# CapacitanceSelector.net
KiCad netlist of a schematic drawn in EAGLE
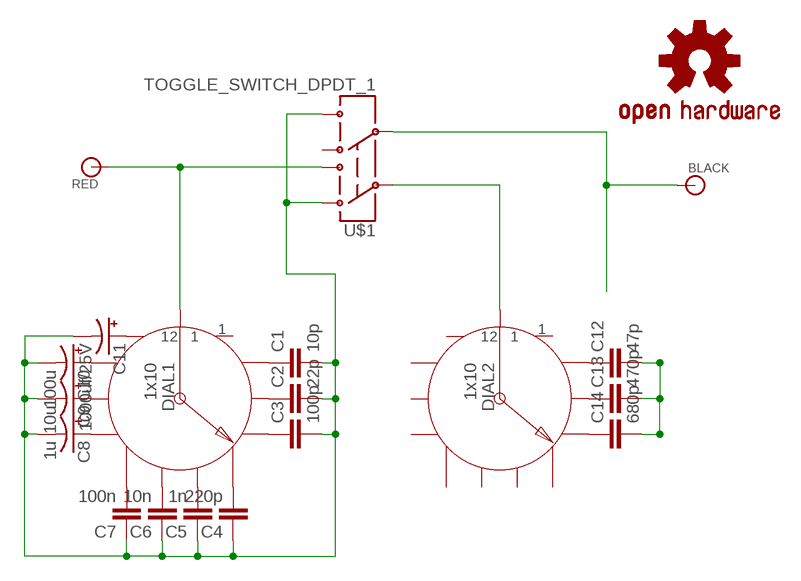
[diagram p0: schematic, sheet 1]

(export (version "E")
  (design (tool "Eeschema 10.0.6"))
  (components
    (comp (ref "BLACK")
      (value "BANANA_CONN")
      (footprint "eagle-import:BANANA_CONN")
      (libsource (lib "eagle-import") (part "BANANA_CONN"))
    )
    (comp (ref "C1")
      (value "10p")
      (footprint "eagle-import:CAP-PTH-SMALL-KIT")
      (libsource (lib "eagle-import") (part "0.1UF-50V-20%(PTH)KIT-EZ"))
    )
    (comp (ref "C2")
      (value "22p")
      (footprint "eagle-import:CAP-PTH-SMALL-KIT")
      (libsource (lib "eagle-import") (part "0.1UF-50V-20%(PTH)KIT-EZ"))
    )
    (comp (ref "C3")
      (value "100p")
      (footprint "eagle-import:CAP-PTH-SMALL-KIT")
      (libsource (lib "eagle-import") (part "0.1UF-50V-20%(PTH)KIT-EZ"))
    )
    (comp (ref "C4")
      (value "220p")
      (footprint "eagle-import:CAP-PTH-SMALL-KIT")
      (libsource (lib "eagle-import") (part "0.1UF-50V-20%(PTH)KIT-EZ"))
    )
    (comp (ref "C5")
      (value "1n")
      (footprint "eagle-import:CAP-PTH-SMALL-KIT")
      (libsource (lib "eagle-import") (part "0.1UF-50V-20%(PTH)KIT-EZ"))
    )
    (comp (ref "C6")
      (value "10n")
      (footprint "eagle-import:CAP-PTH-SMALL-KIT")
      (libsource (lib "eagle-import") (part "0.1UF-50V-20%(PTH)KIT-EZ"))
    )
    (comp (ref "C7")
      (value "100n")
      (footprint "eagle-import:CAP-PTH-SMALL-KIT")
      (libsource (lib "eagle-import") (part "0.1UF-50V-20%(PTH)KIT-EZ"))
    )
    (comp (ref "C8")
      (value "1u")
      (footprint "eagle-import:CPOL-RADIAL-10UF-25V-KIT")
      (libsource (lib "eagle-import") (part "10UF-25V-20%(PTH)KIT"))
    )
    (comp (ref "C9")
      (value "10u")
      (footprint "eagle-import:CPOL-RADIAL-10UF-25V-KIT")
      (libsource (lib "eagle-import") (part "10UF-25V-20%(PTH)KIT"))
    )
    (comp (ref "C10")
      (value "100u")
      (footprint "eagle-import:CPOL-RADIAL-10UF-25V-KIT")
      (libsource (lib "eagle-import") (part "10UF-25V-20%(PTH)KIT"))
    )
    (comp (ref "C11")
      (value "1000uf/25V")
      (footprint "eagle-import:CPOL-RADIAL-1000UF-25V-KIT")
      (libsource (lib "eagle-import") (part "1000UF-25V(PTH)KIT"))
    )
    (comp (ref "C12")
      (value "47p")
      (footprint "eagle-import:AXIAL-5MM")
      (libsource (lib "eagle-import") (part "CAP_"))
    )
    (comp (ref "C13")
      (value "470p")
      (footprint "eagle-import:CAP-PTH-SMALL-KIT")
      (libsource (lib "eagle-import") (part "0.1UF-50V-20%(PTH)KIT-EZ"))
    )
    (comp (ref "C14")
      (value "680p")
      (footprint "eagle-import:CAP-PTH-SMALL-KIT")
      (libsource (lib "eagle-import") (part "0.1UF-50V-20%(PTH)KIT-EZ"))
    )
    (comp (ref "DIAL1")
      (value "1x10")
      (footprint "eagle-import:ROTARY_SWITCH_1X12")
      (libsource (lib "eagle-import") (part "SWITCH_ROTARY_1X12"))
    )
    (comp (ref "DIAL2")
      (value "1x10")
      (footprint "eagle-import:ROTARY_SWITCH_1X12")
      (libsource (lib "eagle-import") (part "SWITCH_ROTARY_1X12"))
    )
    (comp (ref "LOGO1")
      (value "OSHW-LOGOL")
      (footprint "eagle-import:OSHW-LOGO-L")
      (libsource (lib "eagle-import") (part "OSHW-LOGOL"))
    )
    (comp (ref "RED")
      (value "BANANA_CONN")
      (footprint "eagle-import:BANANA_CONN")
      (libsource (lib "eagle-import") (part "BANANA_CONN"))
    )
    (comp (ref "U$1")
      (value "TOGGLE_SWITCH_DPDT_1")
      (footprint "eagle-import:TOGGLE_SWITCH_1")
      (libsource (lib "eagle-import") (part "TOGGLE_SWITCH_DPDT_1"))
    )
  )
  (nets
    (net (code "1") (name "Net-(BLACK-1)") (class "Default")
      (node (ref "BLACK") (pin "P$1") (pinfunction "1_P$1") (pintype "passive"))
      (node (ref "U$1") (pin "P$4") (pinfunction "5_P$4") (pintype "bidirectional"))
    )
    (net (code "2") (name "Net-(C1-Pad1)") (class "Default")
      (node (ref "C1") (pin "1") (pinfunction "1_1") (pintype "passive"))
      (node (ref "DIAL1") (pin "2") (pinfunction "2_2") (pintype "bidirectional"))
    )
    (net (code "3") (name "Net-(C2-Pad1)") (class "Default")
      (node (ref "C2") (pin "1") (pinfunction "1_1") (pintype "passive"))
      (node (ref "DIAL1") (pin "3") (pinfunction "3_3") (pintype "bidirectional"))
    )
    (net (code "4") (name "Net-(C3-Pad1)") (class "Default")
      (node (ref "C3") (pin "1") (pinfunction "1_1") (pintype "passive"))
      (node (ref "DIAL1") (pin "4") (pinfunction "4_4") (pintype "bidirectional"))
    )
    (net (code "5") (name "Net-(C4-Pad2)") (class "Default")
      (node (ref "C4") (pin "2") (pinfunction "2_2") (pintype "passive"))
      (node (ref "DIAL1") (pin "5") (pinfunction "5_5") (pintype "bidirectional"))
    )
    (net (code "6") (name "Net-(C5-Pad2)") (class "Default")
      (node (ref "C5") (pin "2") (pinfunction "2_2") (pintype "passive"))
      (node (ref "DIAL1") (pin "6") (pinfunction "6_6") (pintype "bidirectional"))
    )
    (net (code "7") (name "Net-(C6-Pad2)") (class "Default")
      (node (ref "C6") (pin "2") (pinfunction "2_2") (pintype "passive"))
      (node (ref "DIAL1") (pin "7") (pinfunction "7_7") (pintype "bidirectional"))
    )
    (net (code "8") (name "Net-(C7-Pad2)") (class "Default")
      (node (ref "C7") (pin "2") (pinfunction "2_2") (pintype "passive"))
      (node (ref "DIAL1") (pin "8") (pinfunction "8_8") (pintype "bidirectional"))
    )
    (net (code "9") (name "Net-(C8-+)") (class "Default")
      (node (ref "C8") (pin "1") (pinfunction "+_1") (pintype "passive"))
      (node (ref "DIAL1") (pin "9") (pinfunction "9_9") (pintype "bidirectional"))
    )
    (net (code "10") (name "Net-(C9-+)") (class "Default")
      (node (ref "C9") (pin "1") (pinfunction "+_1") (pintype "passive"))
      (node (ref "DIAL1") (pin "10") (pinfunction "10_10") (pintype "bidirectional"))
    )
    (net (code "11") (name "Net-(C10-+)") (class "Default")
      (node (ref "C10") (pin "1") (pinfunction "+_1") (pintype "passive"))
      (node (ref "DIAL1") (pin "11") (pinfunction "11_11") (pintype "bidirectional"))
    )
    (net (code "12") (name "Net-(C10--)") (class "Default")
      (node (ref "C1") (pin "2") (pinfunction "2_2") (pintype "passive"))
      (node (ref "C10") (pin "2") (pinfunction "-_2") (pintype "passive"))
      (node (ref "C11") (pin "-") (pinfunction "-_-") (pintype "passive"))
      (node (ref "C2") (pin "2") (pinfunction "2_2") (pintype "passive"))
      (node (ref "C3") (pin "2") (pinfunction "2_2") (pintype "passive"))
      (node (ref "C4") (pin "1") (pinfunction "1_1") (pintype "passive"))
      (node (ref "C5") (pin "1") (pinfunction "1_1") (pintype "passive"))
      (node (ref "C6") (pin "1") (pinfunction "1_1") (pintype "passive"))
      (node (ref "C7") (pin "1") (pinfunction "1_1") (pintype "passive"))
      (node (ref "C8") (pin "2") (pinfunction "-_2") (pintype "passive"))
      (node (ref "C9") (pin "2") (pinfunction "-_2") (pintype "passive"))
      (node (ref "U$1") (pin "P$1") (pinfunction "1_P$1") (pintype "bidirectional"))
      (node (ref "U$1") (pin "P$6") (pinfunction "6_P$6") (pintype "bidirectional"))
    )
    (net (code "13") (name "Net-(C11-Pad+)") (class "Default")
      (node (ref "C11") (pin "+") (pinfunction "+_+") (pintype "passive"))
      (node (ref "DIAL1") (pin "12") (pinfunction "12_12") (pintype "bidirectional"))
    )
    (net (code "14") (name "Net-(C12-1)") (class "Default")
      (node (ref "C12") (pin "P$1") (pinfunction "1_P$1") (pintype "passive"))
      (node (ref "DIAL2") (pin "2") (pinfunction "2_2") (pintype "bidirectional"))
    )
    (net (code "15") (name "Net-(C12-2)") (class "Default")
      (node (ref "C12") (pin "P$2") (pinfunction "2_P$2") (pintype "passive"))
      (node (ref "C13") (pin "2") (pinfunction "2_2") (pintype "passive"))
      (node (ref "C14") (pin "2") (pinfunction "2_2") (pintype "passive"))
    )
    (net (code "16") (name "Net-(C13-Pad1)") (class "Default")
      (node (ref "C13") (pin "1") (pinfunction "1_1") (pintype "passive"))
      (node (ref "DIAL2") (pin "3") (pinfunction "3_3") (pintype "bidirectional"))
    )
    (net (code "17") (name "Net-(C14-Pad1)") (class "Default")
      (node (ref "C14") (pin "1") (pinfunction "1_1") (pintype "passive"))
      (node (ref "DIAL2") (pin "4") (pinfunction "4_4") (pintype "bidirectional"))
    )
    (net (code "18") (name "Net-(RED-1)") (class "Default")
      (node (ref "DIAL1") (pin "COMMON") (pinfunction "COMMON_COMMON") (pintype "bidirectional"))
      (node (ref "RED") (pin "P$1") (pinfunction "1_P$1") (pintype "passive"))
      (node (ref "U$1") (pin "P$2") (pinfunction "3_P$2") (pintype "bidirectional"))
    )
    (net (code "19") (name "Net-(U$1-2)") (class "Default")
      (node (ref "DIAL2") (pin "COMMON") (pinfunction "COMMON_COMMON") (pintype "bidirectional"))
      (node (ref "U$1") (pin "P$3") (pinfunction "2_P$3") (pintype "bidirectional"))
    )
    (net (code "20") (name "unconnected-(DIAL1-Pad1)") (class "Default")
      (node (ref "DIAL1") (pin "1") (pinfunction "1_1") (pintype "bidirectional"))
    )
    (net (code "21") (name "unconnected-(DIAL2-Pad1)") (class "Default")
      (node (ref "DIAL2") (pin "1") (pinfunction "1_1") (pintype "bidirectional"))
    )
    (net (code "22") (name "unconnected-(DIAL2-Pad5)") (class "Default")
      (node (ref "DIAL2") (pin "5") (pinfunction "5_5") (pintype "bidirectional"))
    )
    (net (code "23") (name "unconnected-(DIAL2-Pad6)") (class "Default")
      (node (ref "DIAL2") (pin "6") (pinfunction "6_6") (pintype "bidirectional"))
    )
    (net (code "24") (name "unconnected-(DIAL2-Pad7)") (class "Default")
      (node (ref "DIAL2") (pin "7") (pinfunction "7_7") (pintype "bidirectional"))
    )
    (net (code "25") (name "unconnected-(DIAL2-Pad8)") (class "Default")
      (node (ref "DIAL2") (pin "8") (pinfunction "8_8") (pintype "bidirectional"))
    )
    (net (code "26") (name "unconnected-(DIAL2-Pad9)") (class "Default")
      (node (ref "DIAL2") (pin "9") (pinfunction "9_9") (pintype "bidirectional"))
    )
    (net (code "27") (name "unconnected-(DIAL2-Pad10)") (class "Default")
      (node (ref "DIAL2") (pin "10") (pinfunction "10_10") (pintype "bidirectional"))
    )
    (net (code "28") (name "unconnected-(DIAL2-Pad11)") (class "Default")
      (node (ref "DIAL2") (pin "11") (pinfunction "11_11") (pintype "bidirectional"))
    )
    (net (code "29") (name "unconnected-(DIAL2-Pad12)") (class "Default")
      (node (ref "DIAL2") (pin "12") (pinfunction "12_12") (pintype "bidirectional"))
    )
    (net (code "30") (name "unconnected-(U$1-4-PadP$5)") (class "Default")
      (node (ref "U$1") (pin "P$5") (pinfunction "4_P$5") (pintype "bidirectional"))
    )
  )
)
